# OpenVSD.net
KiCad netlist of a schematic drawn in EAGLE
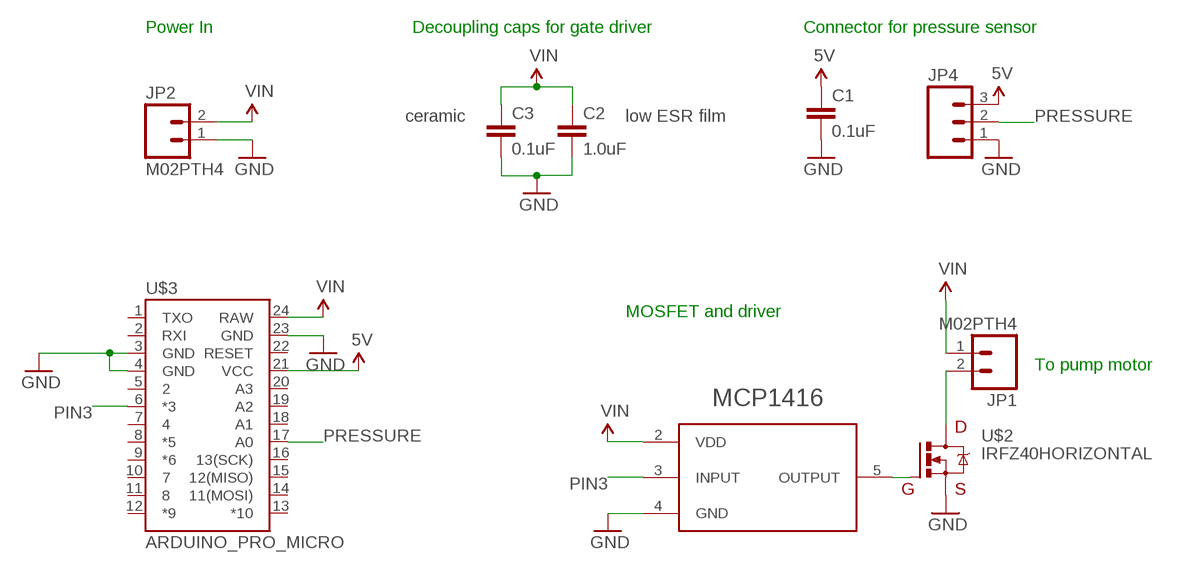
[diagram p0: schematic, sheet 1]

(export (version "E")
  (design (tool "Eeschema 10.0.6"))
  (components
    (comp (ref "C1")
      (value "0.1uF")
      (footprint "eagle-import:0603-CAP")
      (libsource (lib "eagle-import") (part "0.1UF-100V-10%(0603)"))
    )
    (comp (ref "C2")
      (value "1.0uF")
      (footprint "eagle-import:0603-CAP")
      (libsource (lib "eagle-import") (part "1.0UF-16V-10%(0603)"))
    )
    (comp (ref "C3")
      (value "0.1uF")
      (footprint "eagle-import:0603-CAP")
      (libsource (lib "eagle-import") (part "0.1UF-100V-10%(0603)"))
    )
    (comp (ref "JP1")
      (value "M02PTH4")
      (footprint "eagle-import:1X02_XTRA_BIG")
      (libsource (lib "eagle-import") (part "M02PTH4"))
    )
    (comp (ref "JP2")
      (value "M02PTH4")
      (footprint "eagle-import:1X02_XTRA_BIG")
      (libsource (lib "eagle-import") (part "M02PTH4"))
    )
    (comp (ref "JP4")
      (value "M03PTH")
      (footprint "eagle-import:1X03")
      (libsource (lib "eagle-import") (part "M03PTH"))
    )
    (comp (ref "U$1")
      (value "MCP1416")
      (footprint "eagle-import:SOT23-5")
      (libsource (lib "eagle-import") (part "MCP1416"))
    )
    (comp (ref "U$2")
      (value "IRFZ40HORIZONTAL")
      (footprint "eagle-import:TO220")
      (libsource (lib "eagle-import") (part "IRFZ40HORIZONTAL"))
    )
    (comp (ref "U$3")
      (value "ARDUINO_PRO_MICRO")
      (footprint "eagle-import:ARDUINO_PRO_MICRO")
      (libsource (lib "eagle-import") (part "ARDUINO_PRO_MICRO"))
    )
  )
  (nets
    (net (code "1") (name "/PIN3") (class "Default")
      (node (ref "U$1") (pin "3") (pinfunction "INPUT_3") (pintype "bidirectional"))
      (node (ref "U$3") (pin "6") (pinfunction "*3_6") (pintype "bidirectional"))
    )
    (net (code "2") (name "/PRESSURE") (class "Default")
      (node (ref "JP4") (pin "2") (pinfunction "2_2") (pintype "passive"))
      (node (ref "U$3") (pin "17") (pinfunction "A0_17") (pintype "bidirectional"))
    )
    (net (code "3") (name "5V") (class "Default")
      (node (ref "C1") (pin "1") (pinfunction "1_1") (pintype "passive"))
      (node (ref "JP4") (pin "3") (pinfunction "3_3") (pintype "passive"))
      (node (ref "U$3") (pin "21") (pinfunction "VCC_21") (pintype "bidirectional"))
    )
    (net (code "4") (name "GND") (class "Default")
      (node (ref "C1") (pin "2") (pinfunction "2_2") (pintype "passive"))
      (node (ref "C2") (pin "2") (pinfunction "2_2") (pintype "passive"))
      (node (ref "C3") (pin "2") (pinfunction "2_2") (pintype "passive"))
      (node (ref "JP2") (pin "1") (pinfunction "1_1") (pintype "passive"))
      (node (ref "JP4") (pin "1") (pinfunction "1_1") (pintype "passive"))
      (node (ref "U$1") (pin "4") (pinfunction "GND_4") (pintype "power_in"))
      (node (ref "U$2") (pin "3") (pinfunction "S_3") (pintype "passive"))
      (node (ref "U$3") (pin "23") (pinfunction "GND_23") (pintype "bidirectional"))
      (node (ref "U$3") (pin "3") (pinfunction "GND_3") (pintype "bidirectional"))
      (node (ref "U$3") (pin "4") (pinfunction "GND_4") (pintype "bidirectional"))
    )
    (net (code "5") (name "Net-(U$1-OUTPUT)") (class "Default")
      (node (ref "U$1") (pin "5") (pinfunction "OUTPUT_5") (pintype "power_in"))
      (node (ref "U$2") (pin "1") (pinfunction "G_1") (pintype "passive"))
    )
    (net (code "6") (name "Net-(U$2-D)") (class "Default")
      (node (ref "JP1") (pin "2") (pinfunction "2_2") (pintype "passive"))
      (node (ref "U$2") (pin "2") (pinfunction "D_2") (pintype "passive"))
    )
    (net (code "7") (name "VIN") (class "Default")
      (node (ref "C2") (pin "1") (pinfunction "1_1") (pintype "passive"))
      (node (ref "C3") (pin "1") (pinfunction "1_1") (pintype "passive"))
      (node (ref "JP1") (pin "1") (pinfunction "1_1") (pintype "passive"))
      (node (ref "JP2") (pin "2") (pinfunction "2_2") (pintype "passive"))
      (node (ref "U$1") (pin "2") (pinfunction "VDD_2") (pintype "power_in"))
      (node (ref "U$3") (pin "24") (pinfunction "RAW_24") (pintype "bidirectional"))
    )
    (net (code "8") (name "unconnected-(U$3-*5-Pad8)") (class "Default")
      (node (ref "U$3") (pin "8") (pinfunction "*5_8") (pintype "bidirectional"))
    )
    (net (code "9") (name "unconnected-(U$3-*6-Pad9)") (class "Default")
      (node (ref "U$3") (pin "9") (pinfunction "*6_9") (pintype "bidirectional"))
    )
    (net (code "10") (name "unconnected-(U$3-*9-Pad12)") (class "Default")
      (node (ref "U$3") (pin "12") (pinfunction "*9_12") (pintype "bidirectional"))
    )
    (net (code "11") (name "unconnected-(U$3-*10-Pad13)") (class "Default")
      (node (ref "U$3") (pin "13") (pinfunction "*10_13") (pintype "bidirectional"))
    )
    (net (code "12") (name "unconnected-(U$3-2-Pad5)") (class "Default")
      (node (ref "U$3") (pin "5") (pinfunction "2_5") (pintype "bidirectional"))
    )
    (net (code "13") (name "unconnected-(U$3-4-Pad7)") (class "Default")
      (node (ref "U$3") (pin "7") (pinfunction "4_7") (pintype "bidirectional"))
    )
    (net (code "14") (name "unconnected-(U$3-7-Pad10)") (class "Default")
      (node (ref "U$3") (pin "10") (pinfunction "7_10") (pintype "bidirectional"))
    )
    (net (code "15") (name "unconnected-(U$3-8-Pad11)") (class "Default")
      (node (ref "U$3") (pin "11") (pinfunction "8_11") (pintype "bidirectional"))
    )
    (net (code "16") (name "unconnected-(U$3-11(MOSI)-Pad14)") (class "Default")
      (node (ref "U$3") (pin "14") (pinfunction "11(MOSI)_14") (pintype "bidirectional"))
    )
    (net (code "17") (name "unconnected-(U$3-12(MISO)-Pad15)") (class "Default")
      (node (ref "U$3") (pin "15") (pinfunction "12(MISO)_15") (pintype "bidirectional"))
    )
    (net (code "18") (name "unconnected-(U$3-13(SCK)-Pad16)") (class "Default")
      (node (ref "U$3") (pin "16") (pinfunction "13(SCK)_16") (pintype "bidirectional"))
    )
    (net (code "19") (name "unconnected-(U$3-A1-Pad18)") (class "Default")
      (node (ref "U$3") (pin "18") (pinfunction "A1_18") (pintype "bidirectional"))
    )
    (net (code "20") (name "unconnected-(U$3-A2-Pad19)") (class "Default")
      (node (ref "U$3") (pin "19") (pinfunction "A2_19") (pintype "bidirectional"))
    )
    (net (code "21") (name "unconnected-(U$3-A3-Pad20)") (class "Default")
      (node (ref "U$3") (pin "20") (pinfunction "A3_20") (pintype "bidirectional"))
    )
    (net (code "22") (name "unconnected-(U$3-RESET-Pad22)") (class "Default")
      (node (ref "U$3") (pin "22") (pinfunction "RESET_22") (pintype "bidirectional"))
    )
    (net (code "23") (name "unconnected-(U$3-RXI-Pad2)") (class "Default")
      (node (ref "U$3") (pin "2") (pinfunction "RXI_2") (pintype "bidirectional"))
    )
    (net (code "24") (name "unconnected-(U$3-TXO-Pad1)") (class "Default")
      (node (ref "U$3") (pin "1") (pinfunction "TXO_1") (pintype "bidirectional"))
    )
  )
)
